# Christmas-Snow-Globe_v21.net
KiCad netlist of a schematic drawn in EAGLE
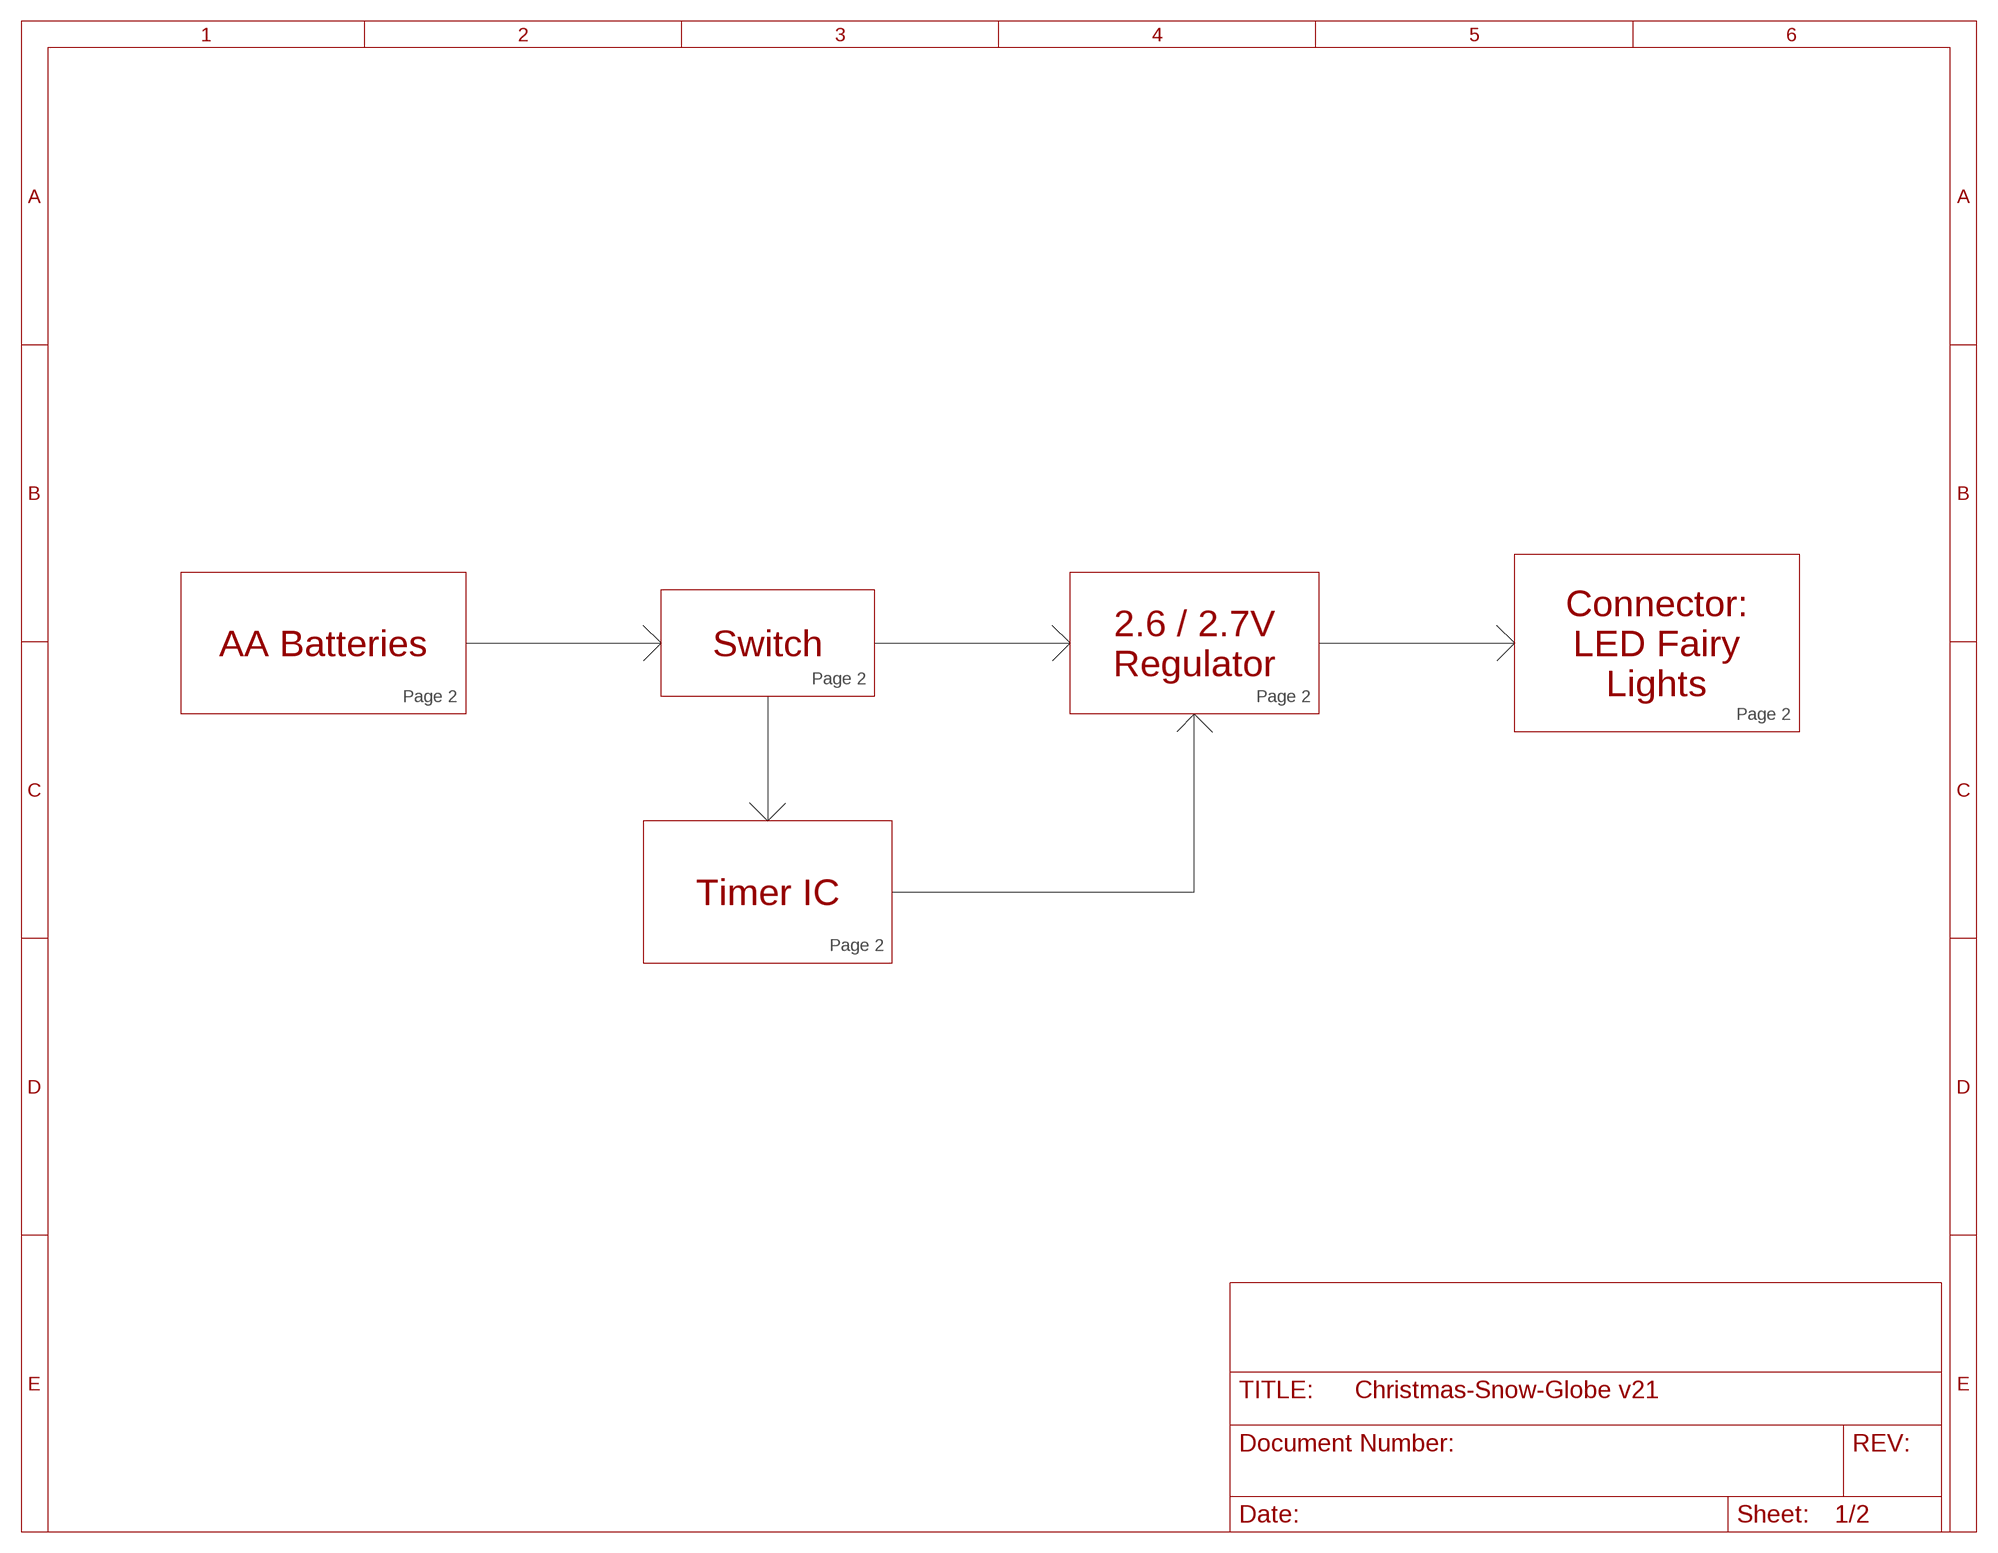
[diagram p0: schematic, sheet 1]
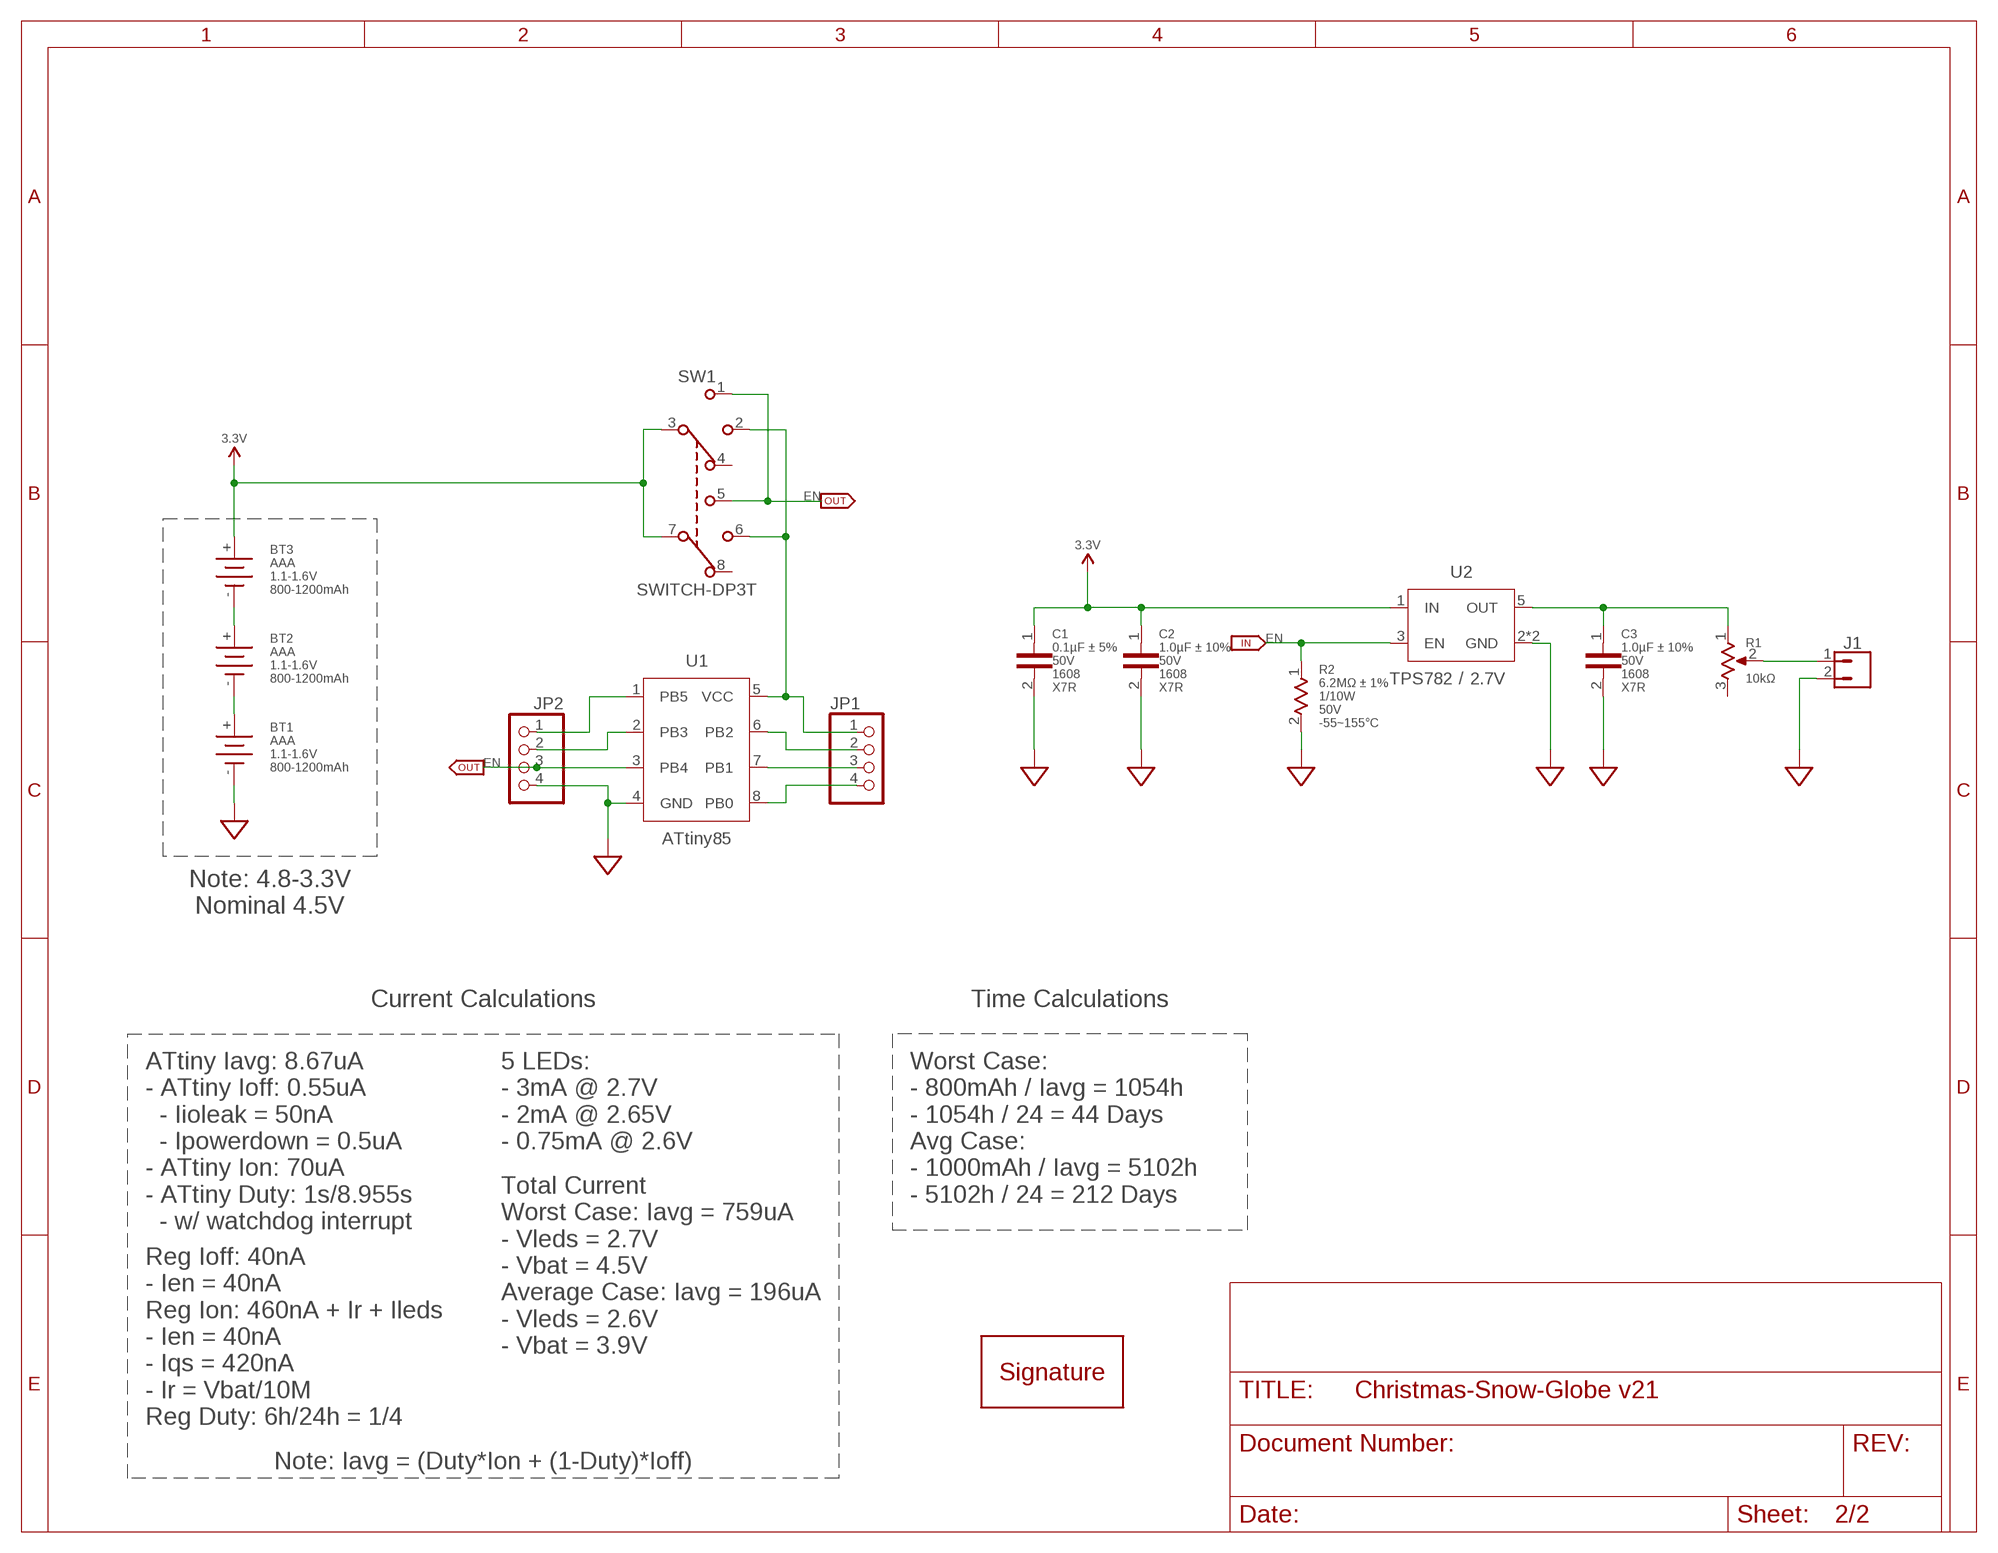
[diagram p1: schematic, sheet 2]

(export (version "E")
  (design (tool "Eeschema 10.0.6"))
  (components
    (comp (ref "BT1")
      (value "AAA")
      (footprint "eagle-import:AAA-CONTACTS")
      (fields (field (name "CAPACITY") "800-1200mAh") (field (name "VOLTAGE") "1.1-1.6V"))
      (libsource (lib "eagle-import") (part "BATTERY-AAAAAA"))
    )
    (comp (ref "BT2")
      (value "AAA")
      (footprint "eagle-import:AAA-CONTACTS")
      (fields (field (name "CAPACITY") "800-1200mAh") (field (name "VOLTAGE") "1.1-1.6V"))
      (libsource (lib "eagle-import") (part "BATTERY-AAAAAA"))
    )
    (comp (ref "BT3")
      (value "AAA")
      (footprint "eagle-import:AAA-CONTACTS")
      (fields (field (name "CAPACITY") "800-1200mAh") (field (name "VOLTAGE") "1.1-1.6V"))
      (libsource (lib "eagle-import") (part "BATTERY-AAAAAA"))
    )
    (comp (ref "C1")
      (value "0.1µF ± 5%")
      (footprint "eagle-import:1608-SEM")
      (fields (field (name "SIZE") "1608") (field (name "TEMPERATURE") "X7R") (field (name "VOLTAGE") "50V"))
      (libsource (lib "eagle-import") (part "CAP-V-1608-0.1UF"))
    )
    (comp (ref "C2")
      (value "1.0µF ± 10%")
      (footprint "eagle-import:1608-SEM")
      (fields (field (name "SIZE") "1608") (field (name "TEMPERATURE") "X7R") (field (name "VOLTAGE") "50V"))
      (libsource (lib "eagle-import") (part "CAP-V-1608-1.0UF"))
    )
    (comp (ref "C3")
      (value "1.0µF ± 10%")
      (footprint "eagle-import:1608-SEM")
      (fields (field (name "SIZE") "1608") (field (name "TEMPERATURE") "X7R") (field (name "VOLTAGE") "50V"))
      (libsource (lib "eagle-import") (part "CAP-V-1608-1.0UF"))
    )
    (comp (ref "J1")
      (value "JST-PH-2")
      (footprint "eagle-import:B2B-PH-K-S")
      (libsource (lib "eagle-import") (part "JST-PH-2"))
    )
    (comp (ref "JP1")
      (value "PINHD-1X4")
      (footprint "eagle-import:1X04")
      (libsource (lib "eagle-import") (part "PINHD-1X4"))
    )
    (comp (ref "JP2")
      (value "PINHD-1X4")
      (footprint "eagle-import:1X04")
      (libsource (lib "eagle-import") (part "PINHD-1X4"))
    )
    (comp (ref "R1")
      (value "10kΩ")
      (footprint "eagle-import:3314J")
      (libsource (lib "eagle-import") (part "TRIMPOT-V-10K"))
    )
    (comp (ref "R2")
      (value "6.2MΩ ± 1%")
      (footprint "eagle-import:1608-SEM")
      (fields
        (field (name "POWER") "1/10W")
        (field (name "TEMPERATURE") "-55~155°C")
        (field (name "VOLTAGE") "50V")
      )
      (libsource (lib "eagle-import") (part "RES-V-1608-6.2M"))
    )
    (comp (ref "SW1")
      (value "SWITCH-DP3T")
      (footprint "eagle-import:EG2301")
      (libsource (lib "eagle-import") (part "SWITCH-DP3T"))
    )
    (comp (ref "U$14")
      (value "SIGNATURE")
      (footprint "eagle-import:SIGNATURE")
      (libsource (lib "eagle-import") (part "SIGNATURE"))
    )
    (comp (ref "U1")
      (value "ATtiny85")
      (footprint "eagle-import:8P3-PDIP")
      (libsource (lib "eagle-import") (part "ATTINNY85"))
    )
    (comp (ref "U2")
      (value "TPS782")
      (footprint "eagle-import:SOT-23-5")
      (fields (field (name "VOLTAGE") "2.7V"))
      (libsource (lib "eagle-import") (part "TPS78X-2.7V"))
    )
  )
  (nets
    (net (code "1") (name "3.3V") (class "Default")
      (node (ref "BT3") (pin "+") (pinfunction "+_+") (pintype "power_in"))
      (node (ref "C1") (pin "1") (pinfunction "P$1_1") (pintype "passive"))
      (node (ref "C2") (pin "1") (pinfunction "P$1_1") (pintype "passive"))
      (node (ref "SW1") (pin "3") (pinfunction "3_3") (pintype "bidirectional"))
      (node (ref "SW1") (pin "7") (pinfunction "7_7") (pintype "bidirectional"))
      (node (ref "U2") (pin "1") (pinfunction "IN_1") (pintype "power_in"))
    )
    (net (code "2") (name "EN") (class "Default")
      (node (ref "JP2") (pin "3") (pinfunction "3_3") (pintype "passive"))
      (node (ref "R2") (pin "1") (pinfunction "1_1") (pintype "passive"))
      (node (ref "SW1") (pin "1") (pinfunction "1_1") (pintype "bidirectional"))
      (node (ref "SW1") (pin "5") (pinfunction "5_5") (pintype "bidirectional"))
      (node (ref "U1") (pin "3") (pinfunction "PB4_3") (pintype "bidirectional"))
      (node (ref "U2") (pin "3") (pinfunction "EN_3") (pintype "input"))
    )
    (net (code "3") (name "GND") (class "Default")
      (node (ref "BT1") (pin "-") (pinfunction "-_-") (pintype "power_in"))
      (node (ref "C1") (pin "2") (pinfunction "P$2_2") (pintype "passive"))
      (node (ref "C2") (pin "2") (pinfunction "P$2_2") (pintype "passive"))
      (node (ref "C3") (pin "2") (pinfunction "P$2_2") (pintype "passive"))
      (node (ref "J1") (pin "2") (pinfunction "2_2") (pintype "bidirectional"))
      (node (ref "JP2") (pin "4") (pinfunction "4_4") (pintype "passive"))
      (node (ref "R2") (pin "2") (pinfunction "2_2") (pintype "passive"))
      (node (ref "U1") (pin "4") (pinfunction "GND_4") (pintype "power_in"))
      (node (ref "U2") (pin "2") (pinfunction "GND_2") (pintype "power_in"))
      (node (ref "U2") (pin "4") (pinfunction "GND_4") (pintype "power_in"))
    )
    (net (code "4") (name "Net-(BT1-Pad+)") (class "Default")
      (node (ref "BT1") (pin "+") (pinfunction "+_+") (pintype "power_in"))
      (node (ref "BT2") (pin "-") (pinfunction "-_-") (pintype "power_in"))
    )
    (net (code "5") (name "Net-(BT2-Pad+)") (class "Default")
      (node (ref "BT2") (pin "+") (pinfunction "+_+") (pintype "power_in"))
      (node (ref "BT3") (pin "-") (pinfunction "-_-") (pintype "power_in"))
    )
    (net (code "6") (name "Net-(C3-P$1)") (class "Default")
      (node (ref "C3") (pin "1") (pinfunction "P$1_1") (pintype "passive"))
      (node (ref "R1") (pin "1") (pinfunction "1_1") (pintype "passive"))
      (node (ref "U2") (pin "5") (pinfunction "OUT_5") (pintype "power_in"))
    )
    (net (code "7") (name "Net-(J1-Pad1)") (class "Default")
      (node (ref "J1") (pin "1") (pinfunction "1_1") (pintype "bidirectional"))
      (node (ref "R1") (pin "2") (pinfunction "2_2") (pintype "passive"))
    )
    (net (code "8") (name "Net-(U1-PB0)") (class "Default")
      (node (ref "JP1") (pin "4") (pinfunction "4_4") (pintype "passive"))
      (node (ref "U1") (pin "8") (pinfunction "PB0_8") (pintype "bidirectional"))
    )
    (net (code "9") (name "Net-(U1-PB1)") (class "Default")
      (node (ref "JP1") (pin "3") (pinfunction "3_3") (pintype "passive"))
      (node (ref "U1") (pin "7") (pinfunction "PB1_7") (pintype "bidirectional"))
    )
    (net (code "10") (name "Net-(U1-PB2)") (class "Default")
      (node (ref "JP1") (pin "2") (pinfunction "2_2") (pintype "passive"))
      (node (ref "U1") (pin "6") (pinfunction "PB2_6") (pintype "bidirectional"))
    )
    (net (code "11") (name "Net-(U1-PB3)") (class "Default")
      (node (ref "JP2") (pin "2") (pinfunction "2_2") (pintype "passive"))
      (node (ref "U1") (pin "2") (pinfunction "PB3_2") (pintype "bidirectional"))
    )
    (net (code "12") (name "Net-(U1-PB5)") (class "Default")
      (node (ref "JP2") (pin "1") (pinfunction "1_1") (pintype "passive"))
      (node (ref "U1") (pin "1") (pinfunction "PB5_1") (pintype "bidirectional"))
    )
    (net (code "13") (name "Net-(U1-VCC)") (class "Default")
      (node (ref "JP1") (pin "1") (pinfunction "1_1") (pintype "passive"))
      (node (ref "SW1") (pin "2") (pinfunction "2_2") (pintype "bidirectional"))
      (node (ref "SW1") (pin "6") (pinfunction "6_6") (pintype "bidirectional"))
      (node (ref "U1") (pin "5") (pinfunction "VCC_5") (pintype "power_in"))
    )
    (net (code "14") (name "unconnected-(R1-Pad3)") (class "Default")
      (node (ref "R1") (pin "3") (pinfunction "3_3") (pintype "passive"))
    )
    (net (code "15") (name "unconnected-(SW1-Pad4)") (class "Default")
      (node (ref "SW1") (pin "4") (pinfunction "4_4") (pintype "bidirectional"))
    )
    (net (code "16") (name "unconnected-(SW1-Pad8)") (class "Default")
      (node (ref "SW1") (pin "8") (pinfunction "8_8") (pintype "bidirectional"))
    )
  )
)
